# 8_RGB_SMD_LEDs.net
KiCad netlist of a schematic drawn in EAGLE
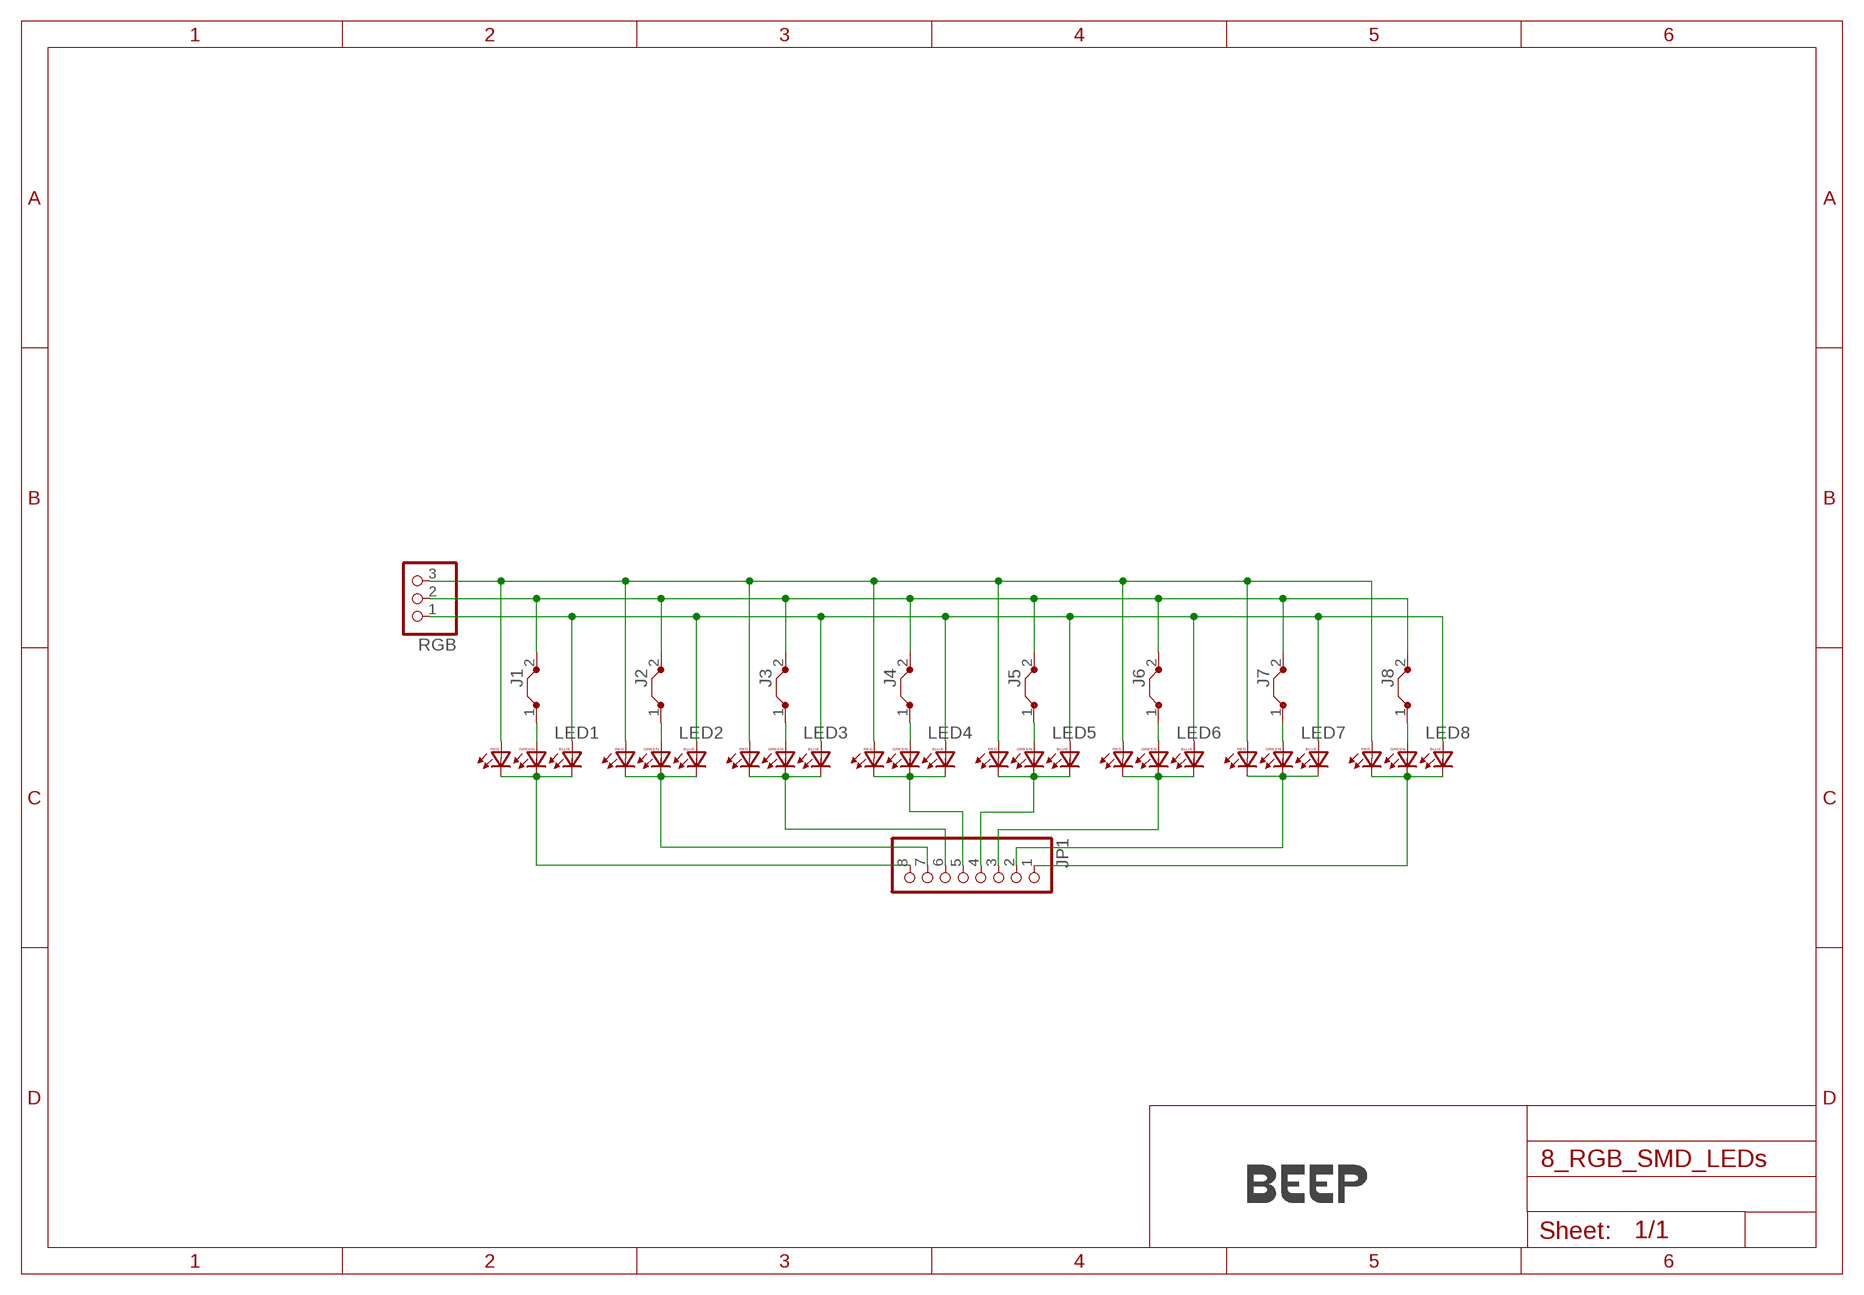
[diagram p0: schematic, sheet 1]

(export (version "E")
  (design (tool "Eeschema 10.0.6"))
  (components
    (comp (ref "J1")
      (value "J7MM")
      (footprint "eagle-import:07")
      (libsource (lib "eagle-import") (part "J7MM"))
    )
    (comp (ref "J2")
      (value "J7MM")
      (footprint "eagle-import:07")
      (libsource (lib "eagle-import") (part "J7MM"))
    )
    (comp (ref "J3")
      (value "J7MM")
      (footprint "eagle-import:07")
      (libsource (lib "eagle-import") (part "J7MM"))
    )
    (comp (ref "J4")
      (value "J7MM")
      (footprint "eagle-import:07")
      (libsource (lib "eagle-import") (part "J7MM"))
    )
    (comp (ref "J5")
      (value "J7MM")
      (footprint "eagle-import:07")
      (libsource (lib "eagle-import") (part "J7MM"))
    )
    (comp (ref "J6")
      (value "J7MM")
      (footprint "eagle-import:07")
      (libsource (lib "eagle-import") (part "J7MM"))
    )
    (comp (ref "J7")
      (value "J7MM")
      (footprint "eagle-import:07")
      (libsource (lib "eagle-import") (part "J7MM"))
    )
    (comp (ref "J8")
      (value "J7MM")
      (footprint "eagle-import:07")
      (libsource (lib "eagle-import") (part "J7MM"))
    )
    (comp (ref "JP1")
      (value "PINHD-1X8")
      (footprint "eagle-import:1X08")
      (libsource (lib "eagle-import") (part "PINHD-1X8"))
    )
    (comp (ref "LED1")
      (value "F503605050")
      (footprint "eagle-import:5050LED")
      (libsource (lib "eagle-import") (part "F503605050"))
    )
    (comp (ref "LED2")
      (value "F503605050")
      (footprint "eagle-import:5050LED")
      (libsource (lib "eagle-import") (part "F503605050"))
    )
    (comp (ref "LED3")
      (value "F503605050")
      (footprint "eagle-import:5050LED")
      (libsource (lib "eagle-import") (part "F503605050"))
    )
    (comp (ref "LED4")
      (value "F503605050")
      (footprint "eagle-import:5050LED")
      (libsource (lib "eagle-import") (part "F503605050"))
    )
    (comp (ref "LED5")
      (value "F503605050")
      (footprint "eagle-import:5050LED")
      (libsource (lib "eagle-import") (part "F503605050"))
    )
    (comp (ref "LED6")
      (value "F503605050")
      (footprint "eagle-import:5050LED")
      (libsource (lib "eagle-import") (part "F503605050"))
    )
    (comp (ref "LED7")
      (value "F503605050")
      (footprint "eagle-import:5050LED")
      (libsource (lib "eagle-import") (part "F503605050"))
    )
    (comp (ref "LED8")
      (value "F503605050")
      (footprint "eagle-import:5050LED")
      (libsource (lib "eagle-import") (part "F503605050"))
    )
    (comp (ref "RGB")
      (value "PINHD-1X3")
      (footprint "eagle-import:1X03")
      (libsource (lib "eagle-import") (part "PINHD-1X3"))
    )
    (comp (ref "U$5")
      (value "LOGO-COPPER7")
      (footprint "eagle-import:COPPER7")
      (libsource (lib "eagle-import") (part "LOGO-COPPER7"))
    )
  )
  (nets
    (net (code "1") (name "Net-(J1-Pad2)") (class "Default")
      (node (ref "J1") (pin "2") (pinfunction "2_2") (pintype "passive"))
      (node (ref "J2") (pin "2") (pinfunction "2_2") (pintype "passive"))
      (node (ref "J3") (pin "2") (pinfunction "2_2") (pintype "passive"))
      (node (ref "J4") (pin "2") (pinfunction "2_2") (pintype "passive"))
      (node (ref "J5") (pin "2") (pinfunction "2_2") (pintype "passive"))
      (node (ref "J6") (pin "2") (pinfunction "2_2") (pintype "passive"))
      (node (ref "J7") (pin "2") (pinfunction "2_2") (pintype "passive"))
      (node (ref "J8") (pin "2") (pinfunction "2_2") (pintype "passive"))
      (node (ref "RGB") (pin "2") (pinfunction "2_2") (pintype "passive"))
    )
    (net (code "2") (name "Net-(LED1-BA)") (class "Default")
      (node (ref "LED1") (pin "B1") (pinfunction "BA_B1") (pintype "passive"))
      (node (ref "LED2") (pin "B1") (pinfunction "BA_B1") (pintype "passive"))
      (node (ref "LED3") (pin "B1") (pinfunction "BA_B1") (pintype "passive"))
      (node (ref "LED4") (pin "B1") (pinfunction "BA_B1") (pintype "passive"))
      (node (ref "LED5") (pin "B1") (pinfunction "BA_B1") (pintype "passive"))
      (node (ref "LED6") (pin "B1") (pinfunction "BA_B1") (pintype "passive"))
      (node (ref "LED7") (pin "B1") (pinfunction "BA_B1") (pintype "passive"))
      (node (ref "LED8") (pin "B1") (pinfunction "BA_B1") (pintype "passive"))
      (node (ref "RGB") (pin "1") (pinfunction "1_1") (pintype "passive"))
    )
    (net (code "3") (name "Net-(LED1-BC)") (class "Default")
      (node (ref "JP1") (pin "8") (pinfunction "8_8") (pintype "passive"))
      (node (ref "LED1") (pin "B2") (pinfunction "BC_B2") (pintype "passive"))
      (node (ref "LED1") (pin "G2") (pinfunction "GC_G2") (pintype "passive"))
      (node (ref "LED1") (pin "R2") (pinfunction "RC_R2") (pintype "passive"))
    )
    (net (code "4") (name "Net-(LED1-GA)") (class "Default")
      (node (ref "J1") (pin "1") (pinfunction "1_1") (pintype "passive"))
      (node (ref "LED1") (pin "G1") (pinfunction "GA_G1") (pintype "passive"))
    )
    (net (code "5") (name "Net-(LED1-RA)") (class "Default")
      (node (ref "LED1") (pin "R1") (pinfunction "RA_R1") (pintype "passive"))
      (node (ref "LED2") (pin "R1") (pinfunction "RA_R1") (pintype "passive"))
      (node (ref "LED3") (pin "R1") (pinfunction "RA_R1") (pintype "passive"))
      (node (ref "LED4") (pin "R1") (pinfunction "RA_R1") (pintype "passive"))
      (node (ref "LED5") (pin "R1") (pinfunction "RA_R1") (pintype "passive"))
      (node (ref "LED6") (pin "R1") (pinfunction "RA_R1") (pintype "passive"))
      (node (ref "LED7") (pin "R1") (pinfunction "RA_R1") (pintype "passive"))
      (node (ref "LED8") (pin "R1") (pinfunction "RA_R1") (pintype "passive"))
      (node (ref "RGB") (pin "3") (pinfunction "3_3") (pintype "passive"))
    )
    (net (code "6") (name "Net-(LED2-BC)") (class "Default")
      (node (ref "JP1") (pin "7") (pinfunction "7_7") (pintype "passive"))
      (node (ref "LED2") (pin "B2") (pinfunction "BC_B2") (pintype "passive"))
      (node (ref "LED2") (pin "G2") (pinfunction "GC_G2") (pintype "passive"))
      (node (ref "LED2") (pin "R2") (pinfunction "RC_R2") (pintype "passive"))
    )
    (net (code "7") (name "Net-(LED2-GA)") (class "Default")
      (node (ref "J2") (pin "1") (pinfunction "1_1") (pintype "passive"))
      (node (ref "LED2") (pin "G1") (pinfunction "GA_G1") (pintype "passive"))
    )
    (net (code "8") (name "Net-(LED3-BC)") (class "Default")
      (node (ref "JP1") (pin "6") (pinfunction "6_6") (pintype "passive"))
      (node (ref "LED3") (pin "B2") (pinfunction "BC_B2") (pintype "passive"))
      (node (ref "LED3") (pin "G2") (pinfunction "GC_G2") (pintype "passive"))
      (node (ref "LED3") (pin "R2") (pinfunction "RC_R2") (pintype "passive"))
    )
    (net (code "9") (name "Net-(LED3-GA)") (class "Default")
      (node (ref "J3") (pin "1") (pinfunction "1_1") (pintype "passive"))
      (node (ref "LED3") (pin "G1") (pinfunction "GA_G1") (pintype "passive"))
    )
    (net (code "10") (name "Net-(LED4-BC)") (class "Default")
      (node (ref "JP1") (pin "5") (pinfunction "5_5") (pintype "passive"))
      (node (ref "LED4") (pin "B2") (pinfunction "BC_B2") (pintype "passive"))
      (node (ref "LED4") (pin "G2") (pinfunction "GC_G2") (pintype "passive"))
      (node (ref "LED4") (pin "R2") (pinfunction "RC_R2") (pintype "passive"))
    )
    (net (code "11") (name "Net-(LED4-GA)") (class "Default")
      (node (ref "J4") (pin "1") (pinfunction "1_1") (pintype "passive"))
      (node (ref "LED4") (pin "G1") (pinfunction "GA_G1") (pintype "passive"))
    )
    (net (code "12") (name "Net-(LED5-BC)") (class "Default")
      (node (ref "JP1") (pin "4") (pinfunction "4_4") (pintype "passive"))
      (node (ref "LED5") (pin "B2") (pinfunction "BC_B2") (pintype "passive"))
      (node (ref "LED5") (pin "G2") (pinfunction "GC_G2") (pintype "passive"))
      (node (ref "LED5") (pin "R2") (pinfunction "RC_R2") (pintype "passive"))
    )
    (net (code "13") (name "Net-(LED5-GA)") (class "Default")
      (node (ref "J5") (pin "1") (pinfunction "1_1") (pintype "passive"))
      (node (ref "LED5") (pin "G1") (pinfunction "GA_G1") (pintype "passive"))
    )
    (net (code "14") (name "Net-(LED6-BC)") (class "Default")
      (node (ref "JP1") (pin "3") (pinfunction "3_3") (pintype "passive"))
      (node (ref "LED6") (pin "B2") (pinfunction "BC_B2") (pintype "passive"))
      (node (ref "LED6") (pin "G2") (pinfunction "GC_G2") (pintype "passive"))
      (node (ref "LED6") (pin "R2") (pinfunction "RC_R2") (pintype "passive"))
    )
    (net (code "15") (name "Net-(LED6-GA)") (class "Default")
      (node (ref "J6") (pin "1") (pinfunction "1_1") (pintype "passive"))
      (node (ref "LED6") (pin "G1") (pinfunction "GA_G1") (pintype "passive"))
    )
    (net (code "16") (name "Net-(LED7-BC)") (class "Default")
      (node (ref "JP1") (pin "2") (pinfunction "2_2") (pintype "passive"))
      (node (ref "LED7") (pin "B2") (pinfunction "BC_B2") (pintype "passive"))
      (node (ref "LED7") (pin "G2") (pinfunction "GC_G2") (pintype "passive"))
      (node (ref "LED7") (pin "R2") (pinfunction "RC_R2") (pintype "passive"))
    )
    (net (code "17") (name "Net-(LED7-GA)") (class "Default")
      (node (ref "J7") (pin "1") (pinfunction "1_1") (pintype "passive"))
      (node (ref "LED7") (pin "G1") (pinfunction "GA_G1") (pintype "passive"))
    )
    (net (code "18") (name "Net-(LED8-BC)") (class "Default")
      (node (ref "JP1") (pin "1") (pinfunction "1_1") (pintype "passive"))
      (node (ref "LED8") (pin "B2") (pinfunction "BC_B2") (pintype "passive"))
      (node (ref "LED8") (pin "G2") (pinfunction "GC_G2") (pintype "passive"))
      (node (ref "LED8") (pin "R2") (pinfunction "RC_R2") (pintype "passive"))
    )
    (net (code "19") (name "Net-(LED8-GA)") (class "Default")
      (node (ref "J8") (pin "1") (pinfunction "1_1") (pintype "passive"))
      (node (ref "LED8") (pin "G1") (pinfunction "GA_G1") (pintype "passive"))
    )
  )
)
